# eib-64-intan-hs_v1_0_revA.net
KiCad netlist of a schematic drawn in EAGLE
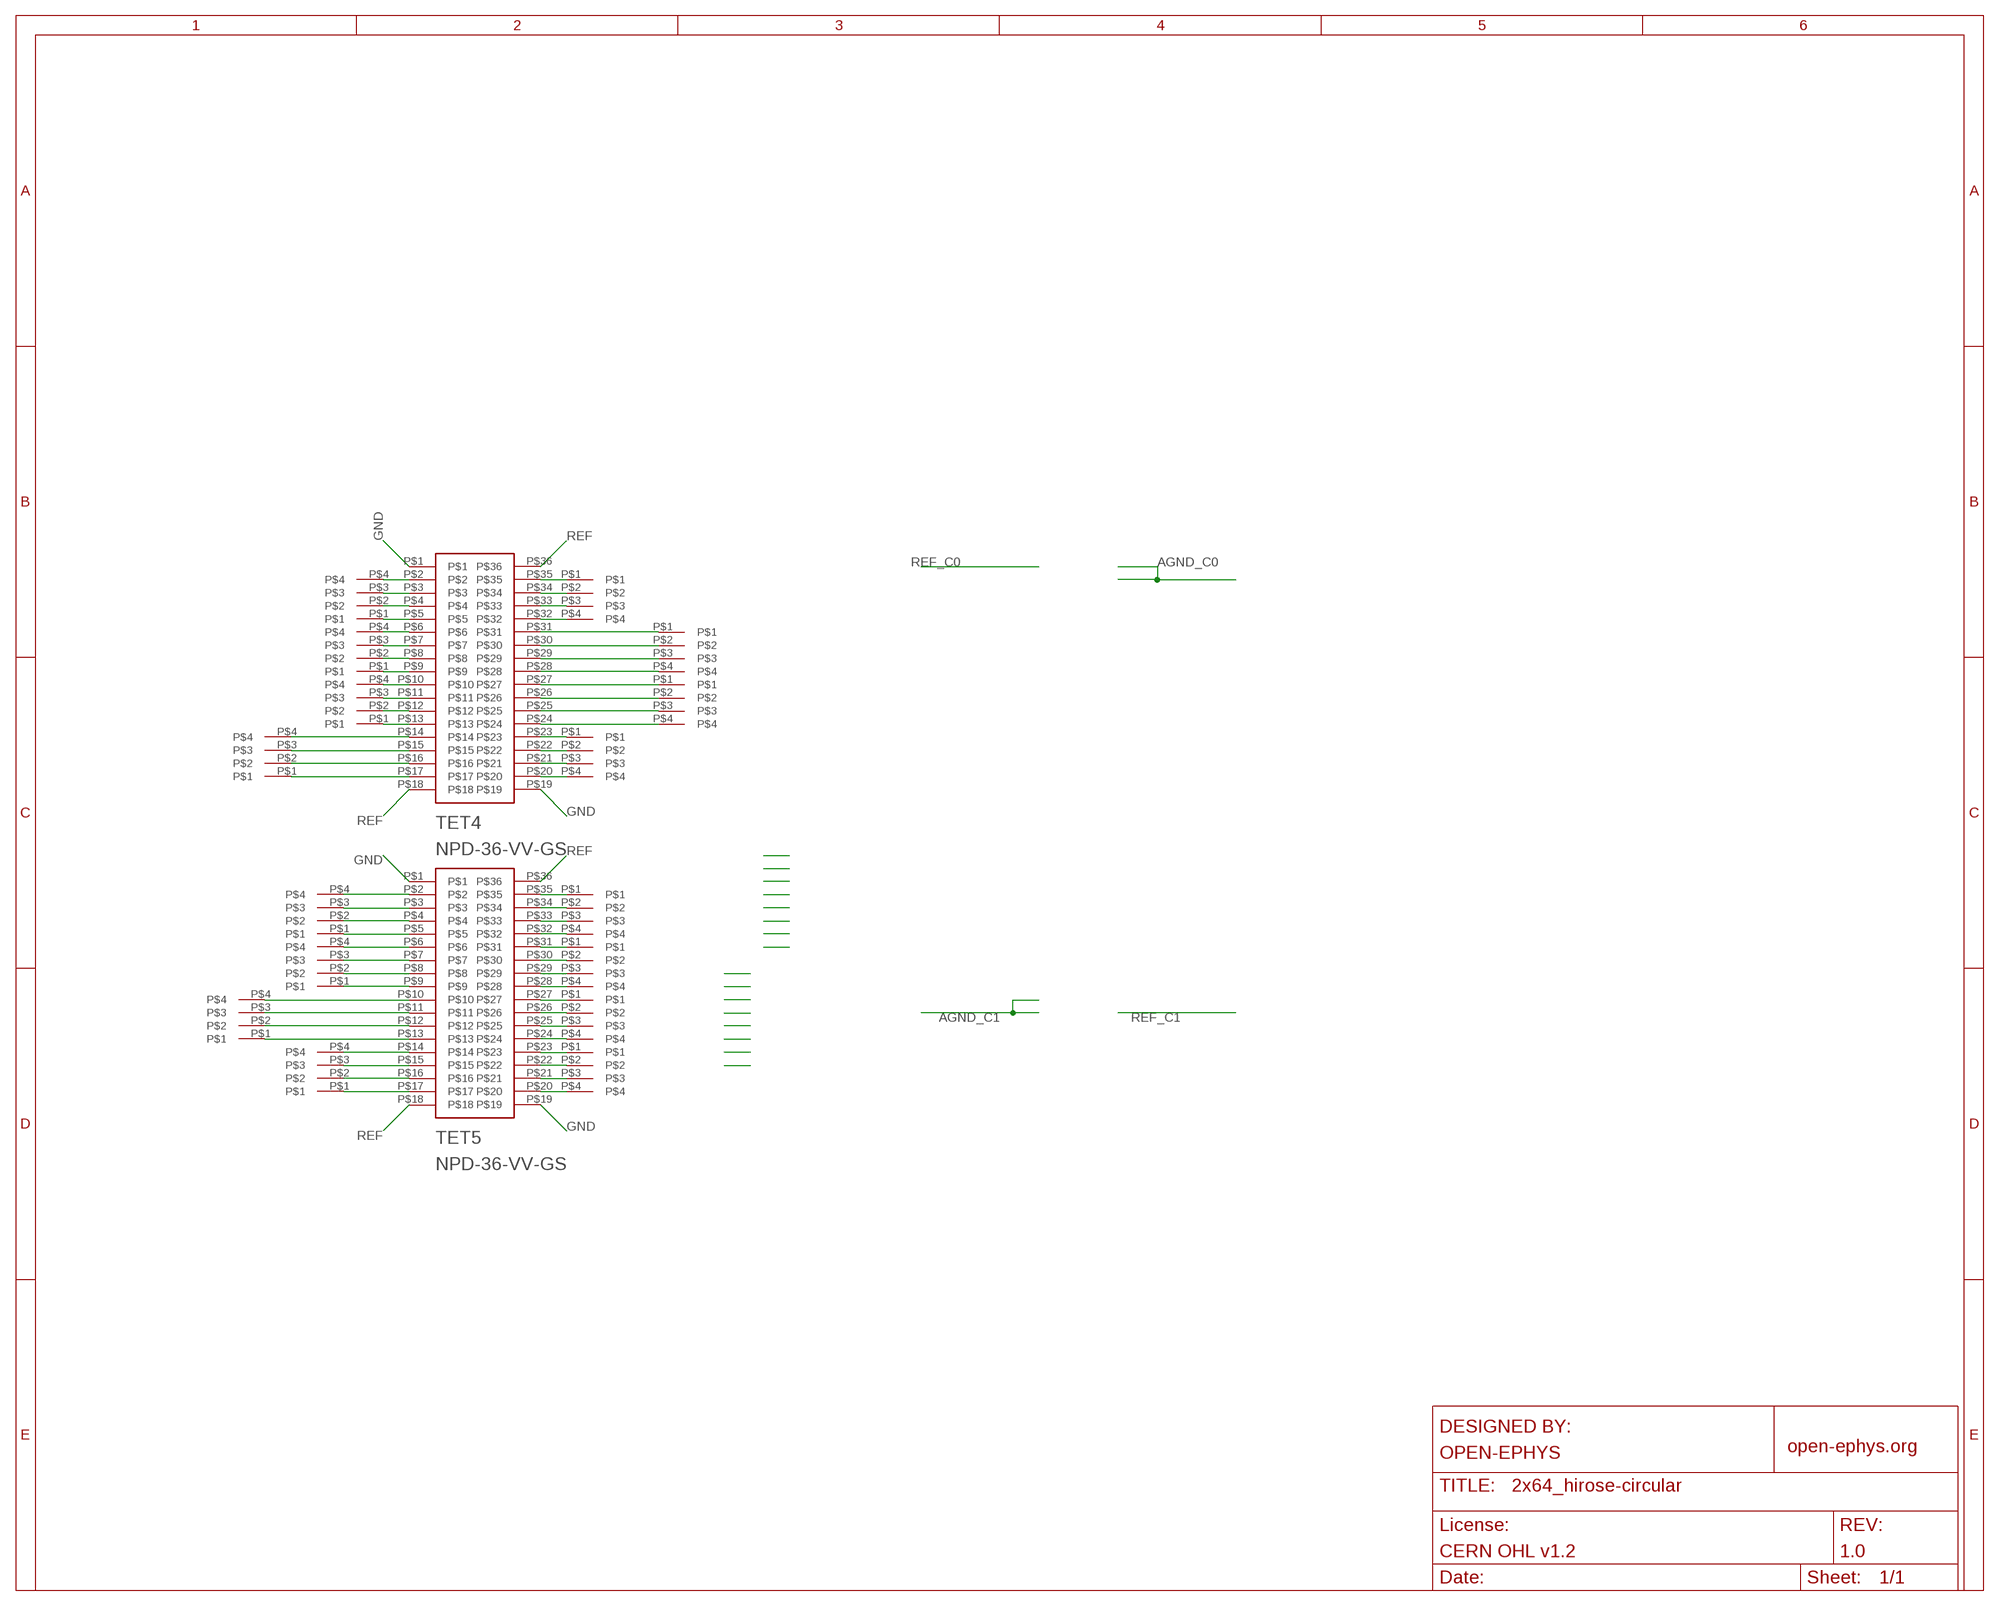
[diagram p0: schematic, sheet 1]

(export (version "E")
  (design (tool "Eeschema 10.0.6"))
  (components
    (comp (ref "TET0")
      (value "0")
      (footprint "eagle-import:TET32")
      (libsource (lib "eagle-import") (part "TET32"))
    )
    (comp (ref "TET1")
      (value "1")
      (footprint "eagle-import:TET32")
      (libsource (lib "eagle-import") (part "TET32"))
    )
    (comp (ref "TET2")
      (value "2")
      (footprint "eagle-import:TET32")
      (libsource (lib "eagle-import") (part "TET32"))
    )
    (comp (ref "TET3")
      (value "3")
      (footprint "eagle-import:TET32")
      (libsource (lib "eagle-import") (part "TET32"))
    )
    (comp (ref "TET4")
      (value "NPD-36-VV-GS")
      (footprint "eagle-import:NPD-36-VV-GS")
      (libsource (lib "eagle-import") (part "NPD-36-VV-GS"))
    )
    (comp (ref "TET5")
      (value "NPD-36-VV-GS")
      (footprint "eagle-import:NPD-36-VV-GS")
      (libsource (lib "eagle-import") (part "NPD-36-VV-GS"))
    )
    (comp (ref "TET8")
      (value "8")
      (footprint "eagle-import:TET32")
      (libsource (lib "eagle-import") (part "TET32"))
    )
    (comp (ref "TET9")
      (value "9")
      (footprint "eagle-import:TET32")
      (libsource (lib "eagle-import") (part "TET32"))
    )
    (comp (ref "TET10")
      (value "10")
      (footprint "eagle-import:TET32")
      (libsource (lib "eagle-import") (part "TET32"))
    )
    (comp (ref "TET11")
      (value "11")
      (footprint "eagle-import:TET32")
      (libsource (lib "eagle-import") (part "TET32"))
    )
    (comp (ref "TET12")
      (value "12")
      (footprint "eagle-import:TET32")
      (libsource (lib "eagle-import") (part "TET32"))
    )
    (comp (ref "TET13")
      (value "13")
      (footprint "eagle-import:TET32")
      (libsource (lib "eagle-import") (part "TET32"))
    )
    (comp (ref "TET14")
      (value "14")
      (footprint "eagle-import:TET32")
      (libsource (lib "eagle-import") (part "TET32"))
    )
    (comp (ref "TET15")
      (value "15")
      (footprint "eagle-import:TET32")
      (libsource (lib "eagle-import") (part "TET32"))
    )
    (comp (ref "TET20")
      (value "20")
      (footprint "eagle-import:TET32")
      (libsource (lib "eagle-import") (part "TET32"))
    )
    (comp (ref "TET21")
      (value "21")
      (footprint "eagle-import:TET32")
      (libsource (lib "eagle-import") (part "TET32"))
    )
    (comp (ref "TET22")
      (value "22")
      (footprint "eagle-import:TET32")
      (libsource (lib "eagle-import") (part "TET32"))
    )
    (comp (ref "TET23")
      (value "23")
      (footprint "eagle-import:TET32")
      (libsource (lib "eagle-import") (part "TET32"))
    )
  )
  (nets
    (net (code "3") (name "/GND") (class "Default")
      (node (ref "TET4") (pin "P$1") (pinfunction "P$1_P$1") (pintype "bidirectional"))
      (node (ref "TET4") (pin "P$19") (pinfunction "P$19_P$19") (pintype "bidirectional"))
      (node (ref "TET5") (pin "P$1") (pinfunction "P$1_P$1") (pintype "bidirectional"))
      (node (ref "TET5") (pin "P$19") (pinfunction "P$19_P$19") (pintype "bidirectional"))
    )
    (net (code "4") (name "/REF") (class "Default")
      (node (ref "TET4") (pin "P$18") (pinfunction "P$18_P$18") (pintype "bidirectional"))
      (node (ref "TET4") (pin "P$36") (pinfunction "P$36_P$36") (pintype "bidirectional"))
      (node (ref "TET5") (pin "P$18") (pinfunction "P$18_P$18") (pintype "bidirectional"))
      (node (ref "TET5") (pin "P$36") (pinfunction "P$36_P$36") (pintype "bidirectional"))
    )
    (net (code "7") (name "Net-(TET0-PadP$1)") (class "Default")
      (node (ref "TET0") (pin "P$1") (pinfunction "P$1_P$1") (pintype "bidirectional"))
      (node (ref "TET4") (pin "P$9") (pinfunction "P$9_P$9") (pintype "bidirectional"))
    )
    (net (code "8") (name "Net-(TET0-PadP$2)") (class "Default")
      (node (ref "TET0") (pin "P$2") (pinfunction "P$2_P$2") (pintype "bidirectional"))
      (node (ref "TET4") (pin "P$8") (pinfunction "P$8_P$8") (pintype "bidirectional"))
    )
    (net (code "9") (name "Net-(TET0-PadP$3)") (class "Default")
      (node (ref "TET0") (pin "P$3") (pinfunction "P$3_P$3") (pintype "bidirectional"))
      (node (ref "TET4") (pin "P$7") (pinfunction "P$7_P$7") (pintype "bidirectional"))
    )
    (net (code "10") (name "Net-(TET0-PadP$4)") (class "Default")
      (node (ref "TET0") (pin "P$4") (pinfunction "P$4_P$4") (pintype "bidirectional"))
      (node (ref "TET4") (pin "P$6") (pinfunction "P$6_P$6") (pintype "bidirectional"))
    )
    (net (code "11") (name "Net-(TET1-PadP$1)") (class "Default")
      (node (ref "TET1") (pin "P$1") (pinfunction "P$1_P$1") (pintype "bidirectional"))
      (node (ref "TET4") (pin "P$5") (pinfunction "P$5_P$5") (pintype "bidirectional"))
    )
    (net (code "12") (name "Net-(TET1-PadP$2)") (class "Default")
      (node (ref "TET1") (pin "P$2") (pinfunction "P$2_P$2") (pintype "bidirectional"))
      (node (ref "TET4") (pin "P$4") (pinfunction "P$4_P$4") (pintype "bidirectional"))
    )
    (net (code "13") (name "Net-(TET1-PadP$3)") (class "Default")
      (node (ref "TET1") (pin "P$3") (pinfunction "P$3_P$3") (pintype "bidirectional"))
      (node (ref "TET4") (pin "P$3") (pinfunction "P$3_P$3") (pintype "bidirectional"))
    )
    (net (code "14") (name "Net-(TET1-PadP$4)") (class "Default")
      (node (ref "TET1") (pin "P$4") (pinfunction "P$4_P$4") (pintype "bidirectional"))
      (node (ref "TET4") (pin "P$2") (pinfunction "P$2_P$2") (pintype "bidirectional"))
    )
    (net (code "15") (name "Net-(TET2-PadP$1)") (class "Default")
      (node (ref "TET2") (pin "P$1") (pinfunction "P$1_P$1") (pintype "bidirectional"))
      (node (ref "TET4") (pin "P$31") (pinfunction "P$31_P$31") (pintype "bidirectional"))
    )
    (net (code "16") (name "Net-(TET2-PadP$2)") (class "Default")
      (node (ref "TET2") (pin "P$2") (pinfunction "P$2_P$2") (pintype "bidirectional"))
      (node (ref "TET4") (pin "P$30") (pinfunction "P$30_P$30") (pintype "bidirectional"))
    )
    (net (code "17") (name "Net-(TET2-PadP$3)") (class "Default")
      (node (ref "TET2") (pin "P$3") (pinfunction "P$3_P$3") (pintype "bidirectional"))
      (node (ref "TET4") (pin "P$29") (pinfunction "P$29_P$29") (pintype "bidirectional"))
    )
    (net (code "18") (name "Net-(TET2-PadP$4)") (class "Default")
      (node (ref "TET2") (pin "P$4") (pinfunction "P$4_P$4") (pintype "bidirectional"))
      (node (ref "TET4") (pin "P$28") (pinfunction "P$28_P$28") (pintype "bidirectional"))
    )
    (net (code "19") (name "Net-(TET3-PadP$1)") (class "Default")
      (node (ref "TET3") (pin "P$1") (pinfunction "P$1_P$1") (pintype "bidirectional"))
      (node (ref "TET4") (pin "P$35") (pinfunction "P$35_P$35") (pintype "bidirectional"))
    )
    (net (code "20") (name "Net-(TET3-PadP$2)") (class "Default")
      (node (ref "TET3") (pin "P$2") (pinfunction "P$2_P$2") (pintype "bidirectional"))
      (node (ref "TET4") (pin "P$34") (pinfunction "P$34_P$34") (pintype "bidirectional"))
    )
    (net (code "21") (name "Net-(TET3-PadP$3)") (class "Default")
      (node (ref "TET3") (pin "P$3") (pinfunction "P$3_P$3") (pintype "bidirectional"))
      (node (ref "TET4") (pin "P$33") (pinfunction "P$33_P$33") (pintype "bidirectional"))
    )
    (net (code "22") (name "Net-(TET3-PadP$4)") (class "Default")
      (node (ref "TET3") (pin "P$4") (pinfunction "P$4_P$4") (pintype "bidirectional"))
      (node (ref "TET4") (pin "P$32") (pinfunction "P$32_P$32") (pintype "bidirectional"))
    )
    (net (code "23") (name "Net-(TET5-PadP$2)") (class "Default")
      (node (ref "TET5") (pin "P$2") (pinfunction "P$2_P$2") (pintype "bidirectional"))
      (node (ref "TET8") (pin "P$4") (pinfunction "P$4_P$4") (pintype "bidirectional"))
    )
    (net (code "24") (name "Net-(TET5-PadP$3)") (class "Default")
      (node (ref "TET5") (pin "P$3") (pinfunction "P$3_P$3") (pintype "bidirectional"))
      (node (ref "TET8") (pin "P$3") (pinfunction "P$3_P$3") (pintype "bidirectional"))
    )
    (net (code "25") (name "Net-(TET5-PadP$4)") (class "Default")
      (node (ref "TET5") (pin "P$4") (pinfunction "P$4_P$4") (pintype "bidirectional"))
      (node (ref "TET8") (pin "P$2") (pinfunction "P$2_P$2") (pintype "bidirectional"))
    )
    (net (code "26") (name "Net-(TET5-PadP$5)") (class "Default")
      (node (ref "TET5") (pin "P$5") (pinfunction "P$5_P$5") (pintype "bidirectional"))
      (node (ref "TET8") (pin "P$1") (pinfunction "P$1_P$1") (pintype "bidirectional"))
    )
    (net (code "27") (name "Net-(TET5-PadP$6)") (class "Default")
      (node (ref "TET5") (pin "P$6") (pinfunction "P$6_P$6") (pintype "bidirectional"))
      (node (ref "TET9") (pin "P$4") (pinfunction "P$4_P$4") (pintype "bidirectional"))
    )
    (net (code "28") (name "Net-(TET5-PadP$7)") (class "Default")
      (node (ref "TET5") (pin "P$7") (pinfunction "P$7_P$7") (pintype "bidirectional"))
      (node (ref "TET9") (pin "P$3") (pinfunction "P$3_P$3") (pintype "bidirectional"))
    )
    (net (code "29") (name "Net-(TET5-PadP$8)") (class "Default")
      (node (ref "TET5") (pin "P$8") (pinfunction "P$8_P$8") (pintype "bidirectional"))
      (node (ref "TET9") (pin "P$2") (pinfunction "P$2_P$2") (pintype "bidirectional"))
    )
    (net (code "30") (name "Net-(TET5-PadP$9)") (class "Default")
      (node (ref "TET5") (pin "P$9") (pinfunction "P$9_P$9") (pintype "bidirectional"))
      (node (ref "TET9") (pin "P$1") (pinfunction "P$1_P$1") (pintype "bidirectional"))
    )
    (net (code "31") (name "Net-(TET10-PadP$1)") (class "Default")
      (node (ref "TET10") (pin "P$1") (pinfunction "P$1_P$1") (pintype "bidirectional"))
      (node (ref "TET5") (pin "P$35") (pinfunction "P$35_P$35") (pintype "bidirectional"))
    )
    (net (code "32") (name "Net-(TET10-PadP$2)") (class "Default")
      (node (ref "TET10") (pin "P$2") (pinfunction "P$2_P$2") (pintype "bidirectional"))
      (node (ref "TET5") (pin "P$34") (pinfunction "P$34_P$34") (pintype "bidirectional"))
    )
    (net (code "33") (name "Net-(TET10-PadP$3)") (class "Default")
      (node (ref "TET10") (pin "P$3") (pinfunction "P$3_P$3") (pintype "bidirectional"))
      (node (ref "TET5") (pin "P$33") (pinfunction "P$33_P$33") (pintype "bidirectional"))
    )
    (net (code "34") (name "Net-(TET10-PadP$4)") (class "Default")
      (node (ref "TET10") (pin "P$4") (pinfunction "P$4_P$4") (pintype "bidirectional"))
      (node (ref "TET5") (pin "P$32") (pinfunction "P$32_P$32") (pintype "bidirectional"))
    )
    (net (code "35") (name "Net-(TET11-PadP$1)") (class "Default")
      (node (ref "TET11") (pin "P$1") (pinfunction "P$1_P$1") (pintype "bidirectional"))
      (node (ref "TET5") (pin "P$31") (pinfunction "P$31_P$31") (pintype "bidirectional"))
    )
    (net (code "36") (name "Net-(TET11-PadP$2)") (class "Default")
      (node (ref "TET11") (pin "P$2") (pinfunction "P$2_P$2") (pintype "bidirectional"))
      (node (ref "TET5") (pin "P$30") (pinfunction "P$30_P$30") (pintype "bidirectional"))
    )
    (net (code "37") (name "Net-(TET11-PadP$3)") (class "Default")
      (node (ref "TET11") (pin "P$3") (pinfunction "P$3_P$3") (pintype "bidirectional"))
      (node (ref "TET5") (pin "P$29") (pinfunction "P$29_P$29") (pintype "bidirectional"))
    )
    (net (code "38") (name "Net-(TET11-PadP$4)") (class "Default")
      (node (ref "TET11") (pin "P$4") (pinfunction "P$4_P$4") (pintype "bidirectional"))
      (node (ref "TET5") (pin "P$28") (pinfunction "P$28_P$28") (pintype "bidirectional"))
    )
    (net (code "39") (name "Net-(TET12-PadP$1)") (class "Default")
      (node (ref "TET12") (pin "P$1") (pinfunction "P$1_P$1") (pintype "bidirectional"))
      (node (ref "TET5") (pin "P$27") (pinfunction "P$27_P$27") (pintype "bidirectional"))
    )
    (net (code "40") (name "Net-(TET12-PadP$2)") (class "Default")
      (node (ref "TET12") (pin "P$2") (pinfunction "P$2_P$2") (pintype "bidirectional"))
      (node (ref "TET5") (pin "P$26") (pinfunction "P$26_P$26") (pintype "bidirectional"))
    )
    (net (code "41") (name "Net-(TET12-PadP$3)") (class "Default")
      (node (ref "TET12") (pin "P$3") (pinfunction "P$3_P$3") (pintype "bidirectional"))
      (node (ref "TET5") (pin "P$25") (pinfunction "P$25_P$25") (pintype "bidirectional"))
    )
    (net (code "42") (name "Net-(TET12-PadP$4)") (class "Default")
      (node (ref "TET12") (pin "P$4") (pinfunction "P$4_P$4") (pintype "bidirectional"))
      (node (ref "TET5") (pin "P$24") (pinfunction "P$24_P$24") (pintype "bidirectional"))
    )
    (net (code "43") (name "Net-(TET13-PadP$1)") (class "Default")
      (node (ref "TET13") (pin "P$1") (pinfunction "P$1_P$1") (pintype "bidirectional"))
      (node (ref "TET5") (pin "P$23") (pinfunction "P$23_P$23") (pintype "bidirectional"))
    )
    (net (code "44") (name "Net-(TET13-PadP$2)") (class "Default")
      (node (ref "TET13") (pin "P$2") (pinfunction "P$2_P$2") (pintype "bidirectional"))
      (node (ref "TET5") (pin "P$22") (pinfunction "P$22_P$22") (pintype "bidirectional"))
    )
    (net (code "45") (name "Net-(TET13-PadP$3)") (class "Default")
      (node (ref "TET13") (pin "P$3") (pinfunction "P$3_P$3") (pintype "bidirectional"))
      (node (ref "TET5") (pin "P$21") (pinfunction "P$21_P$21") (pintype "bidirectional"))
    )
    (net (code "46") (name "Net-(TET13-PadP$4)") (class "Default")
      (node (ref "TET13") (pin "P$4") (pinfunction "P$4_P$4") (pintype "bidirectional"))
      (node (ref "TET5") (pin "P$20") (pinfunction "P$20_P$20") (pintype "bidirectional"))
    )
    (net (code "47") (name "Net-(TET14-PadP$1)") (class "Default")
      (node (ref "TET14") (pin "P$1") (pinfunction "P$1_P$1") (pintype "bidirectional"))
      (node (ref "TET5") (pin "P$13") (pinfunction "P$13_P$13") (pintype "bidirectional"))
    )
    (net (code "48") (name "Net-(TET14-PadP$2)") (class "Default")
      (node (ref "TET14") (pin "P$2") (pinfunction "P$2_P$2") (pintype "bidirectional"))
      (node (ref "TET5") (pin "P$12") (pinfunction "P$12_P$12") (pintype "bidirectional"))
    )
    (net (code "49") (name "Net-(TET14-PadP$3)") (class "Default")
      (node (ref "TET14") (pin "P$3") (pinfunction "P$3_P$3") (pintype "bidirectional"))
      (node (ref "TET5") (pin "P$11") (pinfunction "P$11_P$11") (pintype "bidirectional"))
    )
    (net (code "50") (name "Net-(TET14-PadP$4)") (class "Default")
      (node (ref "TET14") (pin "P$4") (pinfunction "P$4_P$4") (pintype "bidirectional"))
      (node (ref "TET5") (pin "P$10") (pinfunction "P$10_P$10") (pintype "bidirectional"))
    )
    (net (code "51") (name "Net-(TET15-PadP$1)") (class "Default")
      (node (ref "TET15") (pin "P$1") (pinfunction "P$1_P$1") (pintype "bidirectional"))
      (node (ref "TET5") (pin "P$17") (pinfunction "P$17_P$17") (pintype "bidirectional"))
    )
    (net (code "52") (name "Net-(TET15-PadP$2)") (class "Default")
      (node (ref "TET15") (pin "P$2") (pinfunction "P$2_P$2") (pintype "bidirectional"))
      (node (ref "TET5") (pin "P$16") (pinfunction "P$16_P$16") (pintype "bidirectional"))
    )
    (net (code "53") (name "Net-(TET15-PadP$3)") (class "Default")
      (node (ref "TET15") (pin "P$3") (pinfunction "P$3_P$3") (pintype "bidirectional"))
      (node (ref "TET5") (pin "P$15") (pinfunction "P$15_P$15") (pintype "bidirectional"))
    )
    (net (code "54") (name "Net-(TET15-PadP$4)") (class "Default")
      (node (ref "TET15") (pin "P$4") (pinfunction "P$4_P$4") (pintype "bidirectional"))
      (node (ref "TET5") (pin "P$14") (pinfunction "P$14_P$14") (pintype "bidirectional"))
    )
    (net (code "55") (name "Net-(TET20-PadP$1)") (class "Default")
      (node (ref "TET20") (pin "P$1") (pinfunction "P$1_P$1") (pintype "bidirectional"))
      (node (ref "TET4") (pin "P$23") (pinfunction "P$23_P$23") (pintype "bidirectional"))
    )
    (net (code "56") (name "Net-(TET20-PadP$2)") (class "Default")
      (node (ref "TET20") (pin "P$2") (pinfunction "P$2_P$2") (pintype "bidirectional"))
      (node (ref "TET4") (pin "P$22") (pinfunction "P$22_P$22") (pintype "bidirectional"))
    )
    (net (code "57") (name "Net-(TET20-PadP$3)") (class "Default")
      (node (ref "TET20") (pin "P$3") (pinfunction "P$3_P$3") (pintype "bidirectional"))
      (node (ref "TET4") (pin "P$21") (pinfunction "P$21_P$21") (pintype "bidirectional"))
    )
    (net (code "58") (name "Net-(TET20-PadP$4)") (class "Default")
      (node (ref "TET20") (pin "P$4") (pinfunction "P$4_P$4") (pintype "bidirectional"))
      (node (ref "TET4") (pin "P$20") (pinfunction "P$20_P$20") (pintype "bidirectional"))
    )
    (net (code "59") (name "Net-(TET21-PadP$1)") (class "Default")
      (node (ref "TET21") (pin "P$1") (pinfunction "P$1_P$1") (pintype "bidirectional"))
      (node (ref "TET4") (pin "P$27") (pinfunction "P$27_P$27") (pintype "bidirectional"))
    )
    (net (code "60") (name "Net-(TET21-PadP$2)") (class "Default")
      (node (ref "TET21") (pin "P$2") (pinfunction "P$2_P$2") (pintype "bidirectional"))
      (node (ref "TET4") (pin "P$26") (pinfunction "P$26_P$26") (pintype "bidirectional"))
    )
    (net (code "61") (name "Net-(TET21-PadP$3)") (class "Default")
      (node (ref "TET21") (pin "P$3") (pinfunction "P$3_P$3") (pintype "bidirectional"))
      (node (ref "TET4") (pin "P$25") (pinfunction "P$25_P$25") (pintype "bidirectional"))
    )
    (net (code "62") (name "Net-(TET21-PadP$4)") (class "Default")
      (node (ref "TET21") (pin "P$4") (pinfunction "P$4_P$4") (pintype "bidirectional"))
      (node (ref "TET4") (pin "P$24") (pinfunction "P$24_P$24") (pintype "bidirectional"))
    )
    (net (code "63") (name "Net-(TET22-PadP$1)") (class "Default")
      (node (ref "TET22") (pin "P$1") (pinfunction "P$1_P$1") (pintype "bidirectional"))
      (node (ref "TET4") (pin "P$17") (pinfunction "P$17_P$17") (pintype "bidirectional"))
    )
    (net (code "64") (name "Net-(TET22-PadP$2)") (class "Default")
      (node (ref "TET22") (pin "P$2") (pinfunction "P$2_P$2") (pintype "bidirectional"))
      (node (ref "TET4") (pin "P$16") (pinfunction "P$16_P$16") (pintype "bidirectional"))
    )
    (net (code "65") (name "Net-(TET22-PadP$3)") (class "Default")
      (node (ref "TET22") (pin "P$3") (pinfunction "P$3_P$3") (pintype "bidirectional"))
      (node (ref "TET4") (pin "P$15") (pinfunction "P$15_P$15") (pintype "bidirectional"))
    )
    (net (code "66") (name "Net-(TET22-PadP$4)") (class "Default")
      (node (ref "TET22") (pin "P$4") (pinfunction "P$4_P$4") (pintype "bidirectional"))
      (node (ref "TET4") (pin "P$14") (pinfunction "P$14_P$14") (pintype "bidirectional"))
    )
    (net (code "67") (name "Net-(TET23-PadP$1)") (class "Default")
      (node (ref "TET23") (pin "P$1") (pinfunction "P$1_P$1") (pintype "bidirectional"))
      (node (ref "TET4") (pin "P$13") (pinfunction "P$13_P$13") (pintype "bidirectional"))
    )
    (net (code "68") (name "Net-(TET23-PadP$2)") (class "Default")
      (node (ref "TET23") (pin "P$2") (pinfunction "P$2_P$2") (pintype "bidirectional"))
      (node (ref "TET4") (pin "P$12") (pinfunction "P$12_P$12") (pintype "bidirectional"))
    )
    (net (code "69") (name "Net-(TET23-PadP$3)") (class "Default")
      (node (ref "TET23") (pin "P$3") (pinfunction "P$3_P$3") (pintype "bidirectional"))
      (node (ref "TET4") (pin "P$11") (pinfunction "P$11_P$11") (pintype "bidirectional"))
    )
    (net (code "70") (name "Net-(TET23-PadP$4)") (class "Default")
      (node (ref "TET23") (pin "P$4") (pinfunction "P$4_P$4") (pintype "bidirectional"))
      (node (ref "TET4") (pin "P$10") (pinfunction "P$10_P$10") (pintype "bidirectional"))
    )
  )
)
